# FoxSense_Schematic.net
KiCad netlist of a schematic drawn in Altium Designer
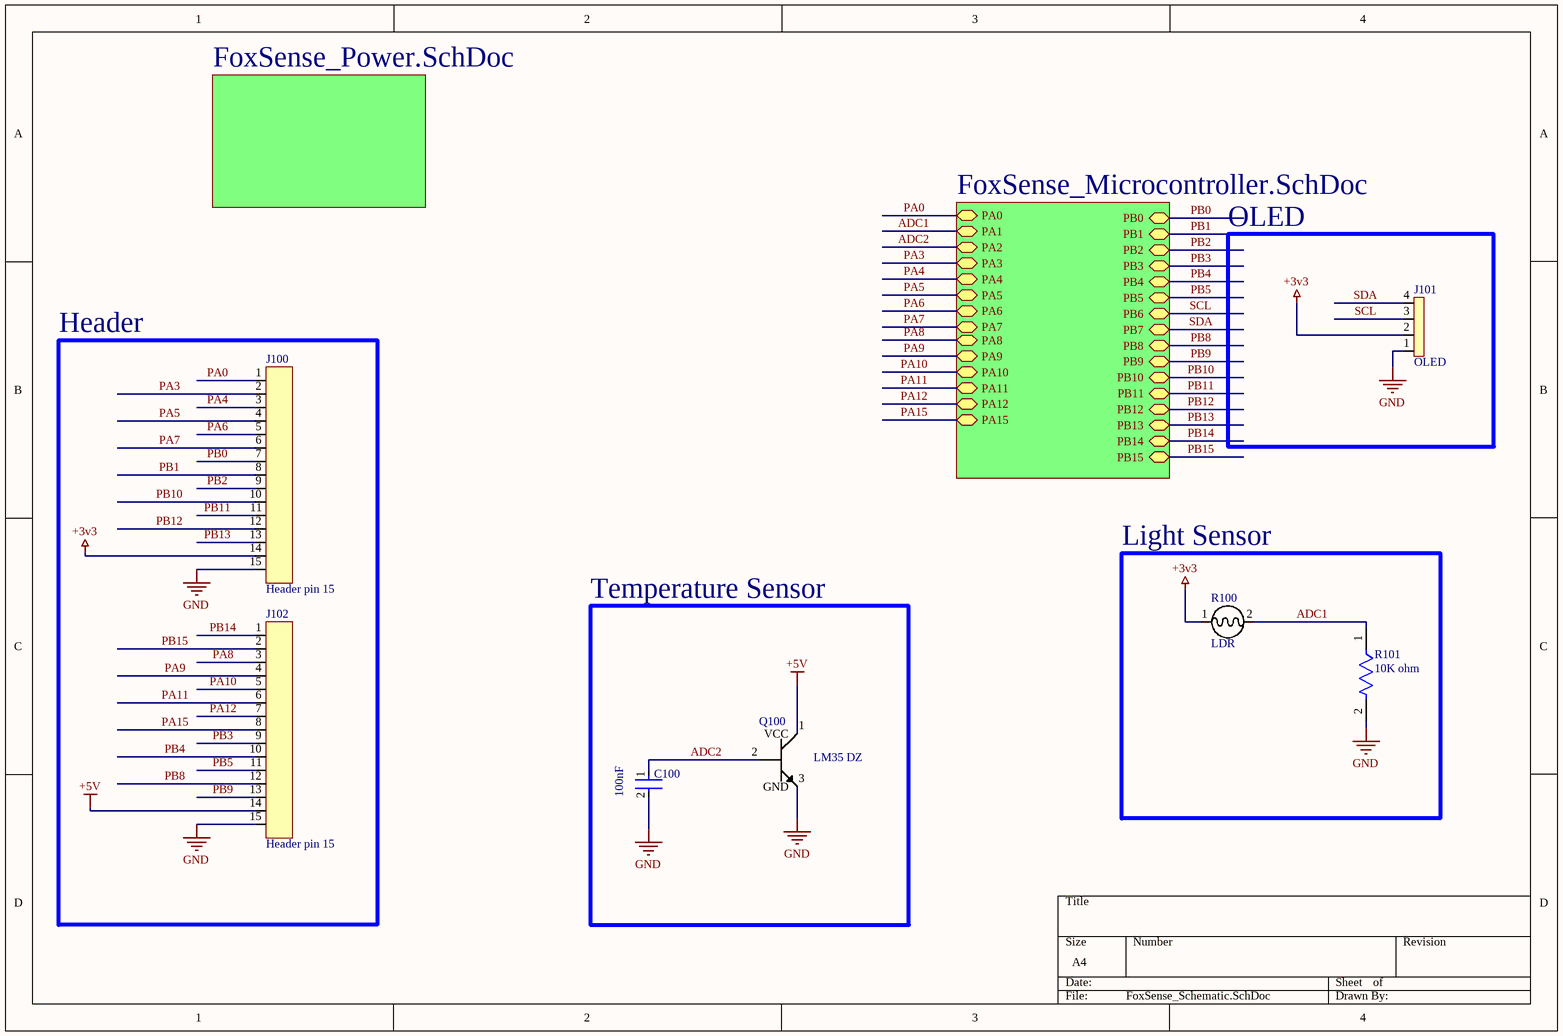
[diagram p0: FoxSense_Schematic.SchDoc]

(export (version "E")
  (design (tool "Eeschema 10.0.6"))
  (components
    (comp (ref "C100")
      (value "100nF")
      (footprint "Capacitor_SMD_0805")
      (description "capacitor smd 0805 100nF")
      (libsource (lib "Fox_Schlib") (part "Capacitor_SMD_0805"))
    )
    (comp (ref "J100")
      (value "Header pin 15")
      (footprint "Header15")
      (libsource (lib "Fox_Schlib") (part "Header15"))
    )
    (comp (ref "J101")
      (value "OLED")
      (footprint "Header4")
      (description "OLED 0..96 inch")
      (libsource (lib "Fox_Schlib") (part "Header4"))
    )
    (comp (ref "J102")
      (value "Header pin 15")
      (footprint "Header15")
      (libsource (lib "Fox_Schlib") (part "Header15"))
    )
    (comp (ref "Q100") (value "LM35 DZ") (footprint "LM35") (libsource (lib "Fox_Schlib") (part "LM35")))
    (comp (ref "R100")
      (value "LDR")
      (footprint "LDR")
      (description "LDR DIP")
      (libsource (lib "Fox_Schlib") (part "LDR"))
    )
    (comp (ref "R101")
      (value "10K ohm")
      (footprint "Resistor_SMD_0805")
      (description "Resistor SMD 0805 10 k ohm")
      (libsource (lib "Fox_Schlib") (part "Resistor_SMD_0805"))
    )
  )
  (nets
    (net (code "1") (name "+3v3") (class "Default")
      (node (ref "J100") (pin "14") (pintype "passive"))
      (node (ref "J101") (pin "2") (pinfunction "2_2") (pintype "passive"))
      (node (ref "R100") (pin "1") (pintype "passive"))
    )
    (net (code "2") (name "+5V") (class "Default")
      (node (ref "J102") (pin "14") (pintype "passive"))
      (node (ref "Q100") (pin "1") (pinfunction "VCC_1") (pintype "passive"))
    )
    (net (code "3") (name "/ADC1") (class "Default")
      (node (ref "R100") (pin "2") (pintype "passive"))
      (node (ref "R101") (pin "1") (pinfunction "1_1") (pintype "passive"))
    )
    (net (code "4") (name "/ADC2") (class "Default")
      (node (ref "C100") (pin "1") (pinfunction "1_1") (pintype "passive"))
      (node (ref "Q100") (pin "2") (pintype "passive"))
    )
    (net (code "5") (name "/PA0") (class "Default") (node (ref "J100") (pin "1") (pintype "passive")))
    (net (code "6") (name "/PA3") (class "Default") (node (ref "J100") (pin "2") (pintype "passive")))
    (net (code "7") (name "/PA4") (class "Default") (node (ref "J100") (pin "3") (pintype "passive")))
    (net (code "8") (name "/PA5") (class "Default") (node (ref "J100") (pin "4") (pintype "passive")))
    (net (code "9") (name "/PA6") (class "Default") (node (ref "J100") (pin "5") (pintype "passive")))
    (net (code "10") (name "/PA7") (class "Default") (node (ref "J100") (pin "6") (pintype "passive")))
    (net (code "11") (name "/PA8") (class "Default") (node (ref "J102") (pin "3") (pintype "passive")))
    (net (code "12") (name "/PA9") (class "Default") (node (ref "J102") (pin "4") (pintype "passive")))
    (net (code "13") (name "/PA10") (class "Default") (node (ref "J102") (pin "5") (pintype "passive")))
    (net (code "14") (name "/PA11") (class "Default") (node (ref "J102") (pin "6") (pintype "passive")))
    (net (code "15") (name "/PA12") (class "Default") (node (ref "J102") (pin "7") (pintype "passive")))
    (net (code "16") (name "/PA15") (class "Default") (node (ref "J102") (pin "8") (pintype "passive")))
    (net (code "17") (name "/PB0") (class "Default") (node (ref "J100") (pin "7") (pintype "passive")))
    (net (code "18") (name "/PB1") (class "Default") (node (ref "J100") (pin "8") (pintype "passive")))
    (net (code "19") (name "/PB2") (class "Default") (node (ref "J100") (pin "9") (pintype "passive")))
    (net (code "20") (name "/PB3") (class "Default") (node (ref "J102") (pin "9") (pintype "passive")))
    (net (code "21") (name "/PB4") (class "Default") (node (ref "J102") (pin "10") (pintype "passive")))
    (net (code "22") (name "/PB5") (class "Default") (node (ref "J102") (pin "11") (pintype "passive")))
    (net (code "23") (name "/PB8") (class "Default") (node (ref "J102") (pin "12") (pintype "passive")))
    (net (code "24") (name "/PB9") (class "Default") (node (ref "J102") (pin "13") (pintype "passive")))
    (net (code "25") (name "/PB10") (class "Default") (node (ref "J100") (pin "10") (pintype "passive")))
    (net (code "26") (name "/PB11") (class "Default") (node (ref "J100") (pin "11") (pintype "passive")))
    (net (code "27") (name "/PB12") (class "Default") (node (ref "J100") (pin "12") (pintype "passive")))
    (net (code "28") (name "/PB13") (class "Default") (node (ref "J100") (pin "13") (pintype "passive")))
    (net (code "29") (name "/PB14") (class "Default") (node (ref "J102") (pin "1") (pintype "passive")))
    (net (code "30") (name "/PB15") (class "Default") (node (ref "J102") (pin "2") (pintype "passive")))
    (net (code "31") (name "/SCL") (class "Default")
      (node (ref "J101") (pin "3") (pinfunction "3_3") (pintype "passive"))
    )
    (net (code "32") (name "/SDA") (class "Default")
      (node (ref "J101") (pin "4") (pinfunction "4_4") (pintype "passive"))
    )
    (net (code "33") (name "GND") (class "Default")
      (node (ref "C100") (pin "2") (pinfunction "2_2") (pintype "passive"))
      (node (ref "J100") (pin "15") (pintype "passive"))
      (node (ref "J101") (pin "1") (pinfunction "1_1") (pintype "passive"))
      (node (ref "J102") (pin "15") (pintype "passive"))
      (node (ref "Q100") (pin "3") (pinfunction "GND_3") (pintype "passive"))
      (node (ref "R101") (pin "2") (pinfunction "2_2") (pintype "passive"))
    )
  )
)
